# GPIO_EXTENDER.net
KiCad netlist of a schematic drawn in Altium Designer
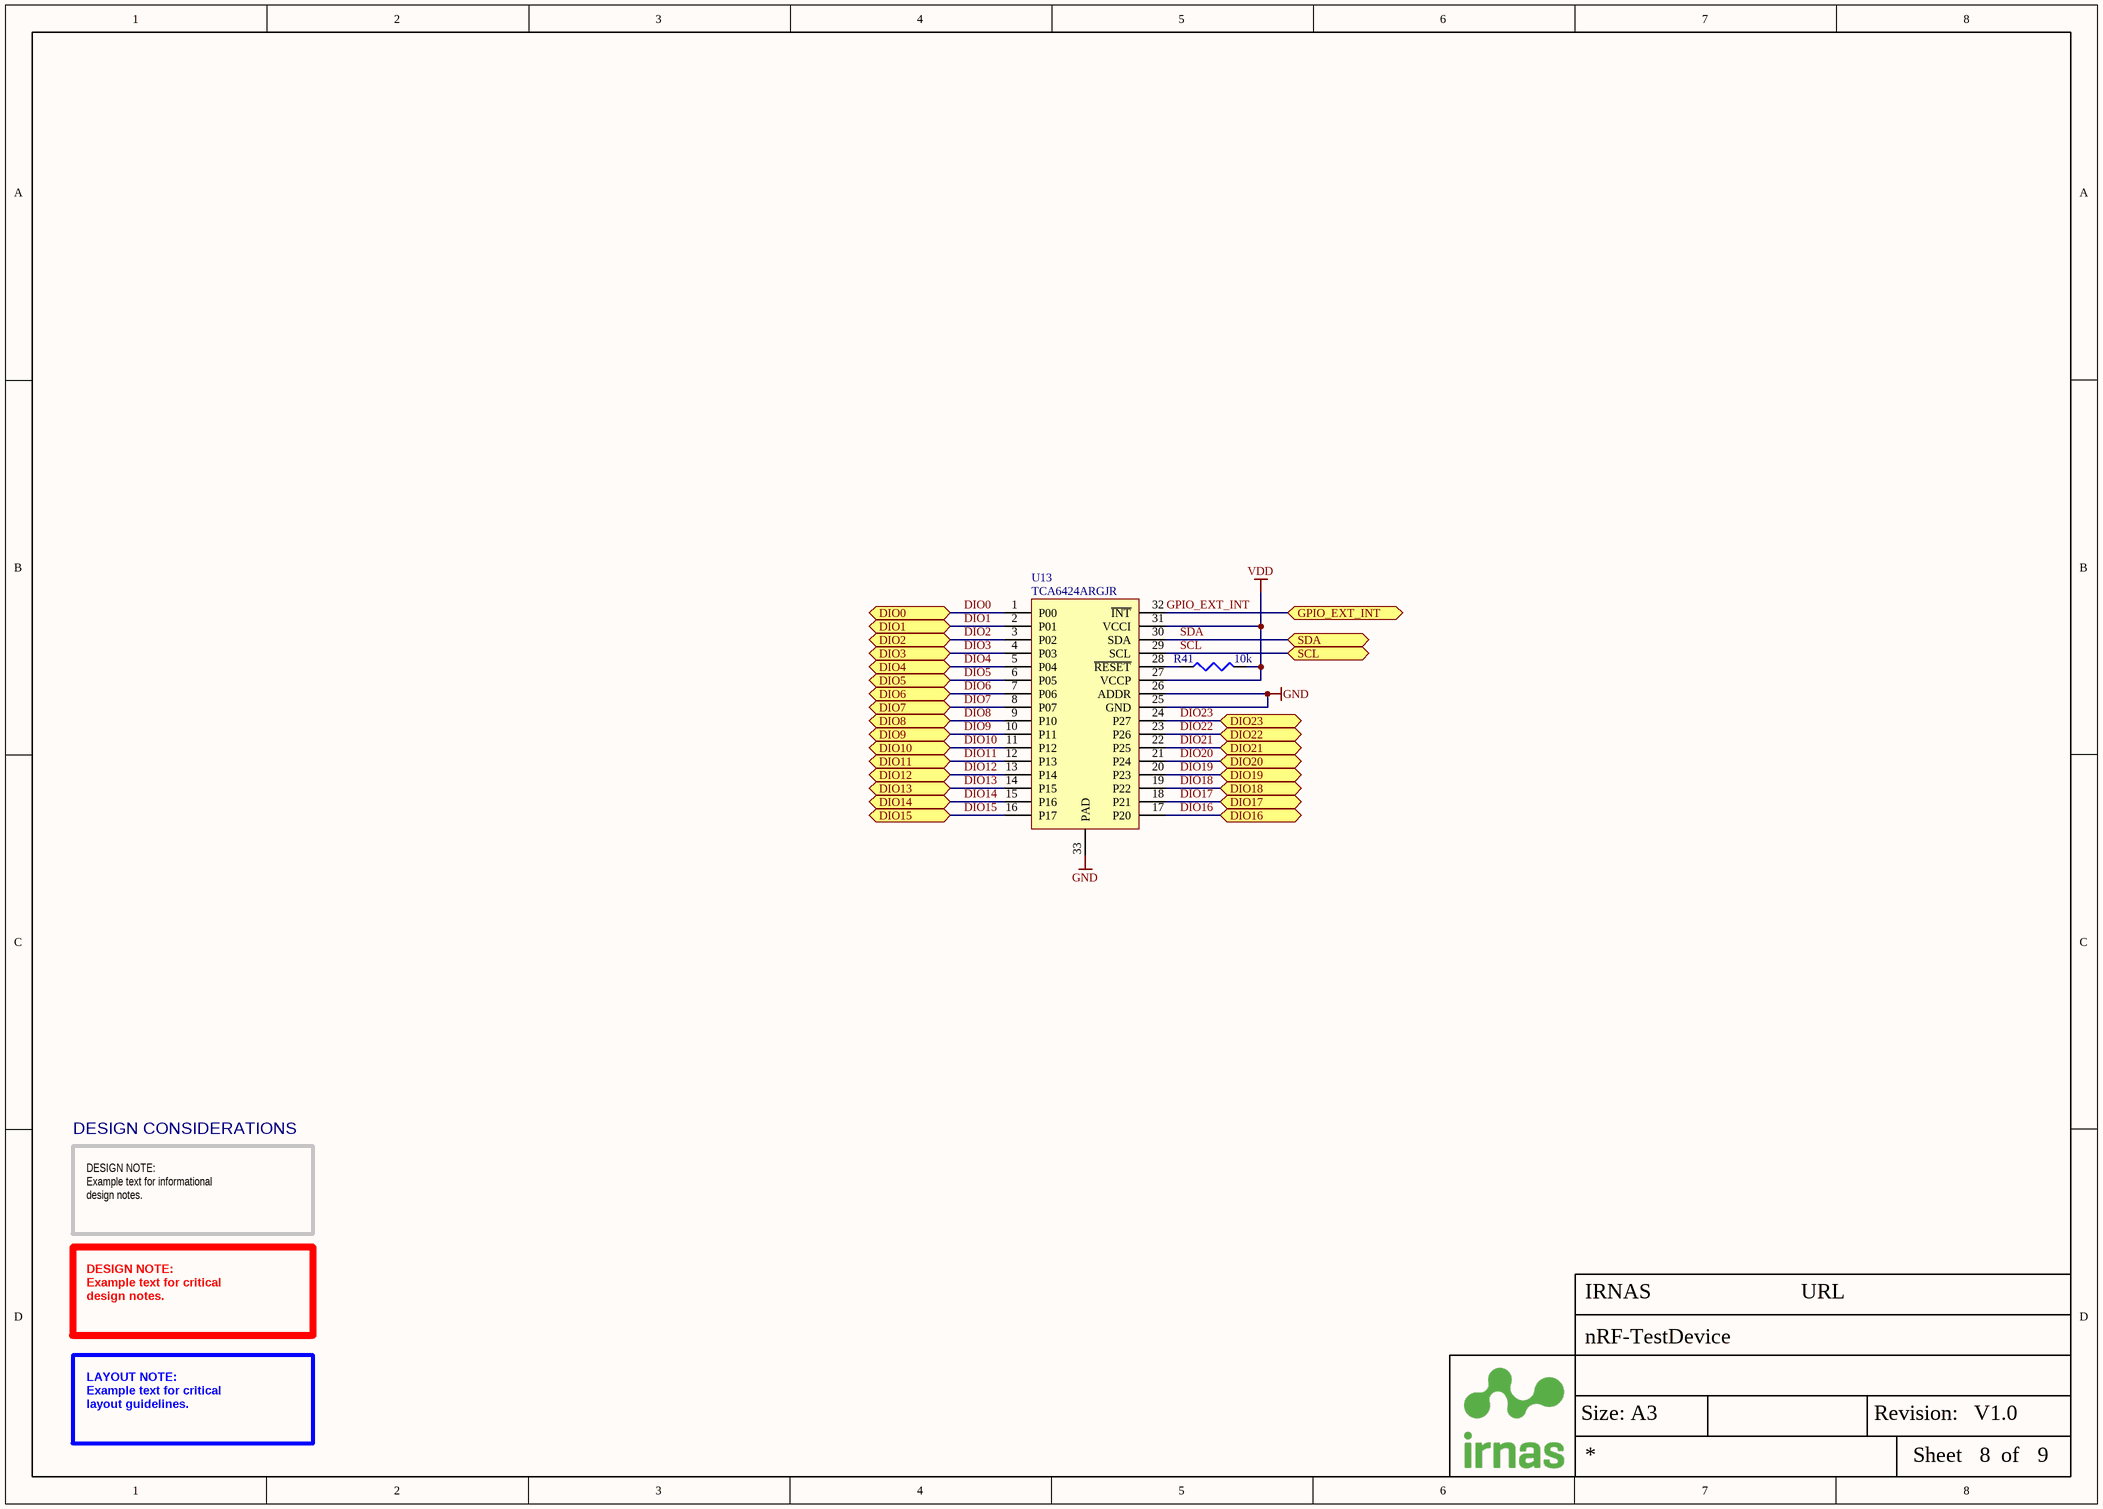
[diagram p0: GPIO_EXTENDER.SchDoc]

(export (version "E")
  (design (tool "Eeschema 10.0.6"))
  (components
    (comp (ref "R41")
      (value "10k")
      (footprint "RES0402")
      (fields
        (field (name "MANUFACTURER") "Multicomp")
        (field (name "MANUFACTURER PART NUMBER") "MCWR04X1002FTL")
        (field (name "TOLERANCE") "1%")
      )
      (libsource (lib "Passive") (part "R - 10k/0402"))
    )
    (comp (ref "U13")
      (value "TCA6424ARGJR")
      (footprint "UQFN 32")
      (description "I/O Expander, 24bit, 400 kHz, I2C, SMBus, 1.65 V, 5.5 V, UQFN")
      (libsource (lib "Active") (part "INT - TCA6424ARGJR"))
    )
  )
  (nets
    (net (code "1") (name "/DIO0") (class "Default")
      (node (ref "U13") (pin "1") (pinfunction "P00_1") (pintype "passive"))
    )
    (net (code "2") (name "/DIO1") (class "Default")
      (node (ref "U13") (pin "2") (pinfunction "P01_2") (pintype "passive"))
    )
    (net (code "3") (name "/DIO2") (class "Default")
      (node (ref "U13") (pin "3") (pinfunction "P02_3") (pintype "passive"))
    )
    (net (code "4") (name "/DIO3") (class "Default")
      (node (ref "U13") (pin "4") (pinfunction "P03_4") (pintype "passive"))
    )
    (net (code "5") (name "/DIO4") (class "Default")
      (node (ref "U13") (pin "5") (pinfunction "P04_5") (pintype "passive"))
    )
    (net (code "6") (name "/DIO5") (class "Default")
      (node (ref "U13") (pin "6") (pinfunction "P05_6") (pintype "passive"))
    )
    (net (code "7") (name "/DIO6") (class "Default")
      (node (ref "U13") (pin "7") (pinfunction "P06_7") (pintype "passive"))
    )
    (net (code "8") (name "/DIO7") (class "Default")
      (node (ref "U13") (pin "8") (pinfunction "P07_8") (pintype "passive"))
    )
    (net (code "9") (name "/DIO8") (class "Default")
      (node (ref "U13") (pin "9") (pinfunction "P10_9") (pintype "passive"))
    )
    (net (code "10") (name "/DIO9") (class "Default")
      (node (ref "U13") (pin "10") (pinfunction "P11_10") (pintype "passive"))
    )
    (net (code "11") (name "/DIO10") (class "Default")
      (node (ref "U13") (pin "11") (pinfunction "P12_11") (pintype "passive"))
    )
    (net (code "12") (name "/DIO11") (class "Default")
      (node (ref "U13") (pin "12") (pinfunction "P13_12") (pintype "passive"))
    )
    (net (code "13") (name "/DIO12") (class "Default")
      (node (ref "U13") (pin "13") (pinfunction "P14_13") (pintype "passive"))
    )
    (net (code "14") (name "/DIO13") (class "Default")
      (node (ref "U13") (pin "14") (pinfunction "P15_14") (pintype "passive"))
    )
    (net (code "15") (name "/DIO14") (class "Default")
      (node (ref "U13") (pin "15") (pinfunction "P16_15") (pintype "passive"))
    )
    (net (code "16") (name "/DIO15") (class "Default")
      (node (ref "U13") (pin "16") (pinfunction "P17_16") (pintype "passive"))
    )
    (net (code "17") (name "/DIO16") (class "Default")
      (node (ref "U13") (pin "17") (pinfunction "P20_17") (pintype "passive"))
    )
    (net (code "18") (name "/DIO17") (class "Default")
      (node (ref "U13") (pin "18") (pinfunction "P21_18") (pintype "passive"))
    )
    (net (code "19") (name "/DIO18") (class "Default")
      (node (ref "U13") (pin "19") (pinfunction "P22_19") (pintype "passive"))
    )
    (net (code "20") (name "/DIO19") (class "Default")
      (node (ref "U13") (pin "20") (pinfunction "P23_20") (pintype "passive"))
    )
    (net (code "21") (name "/DIO20") (class "Default")
      (node (ref "U13") (pin "21") (pinfunction "P24_21") (pintype "passive"))
    )
    (net (code "22") (name "/DIO21") (class "Default")
      (node (ref "U13") (pin "22") (pinfunction "P25_22") (pintype "passive"))
    )
    (net (code "23") (name "/DIO22") (class "Default")
      (node (ref "U13") (pin "23") (pinfunction "P26_23") (pintype "passive"))
    )
    (net (code "24") (name "/DIO23") (class "Default")
      (node (ref "U13") (pin "24") (pinfunction "P27_24") (pintype "passive"))
    )
    (net (code "25") (name "/GPIO_EXT_INT") (class "Default")
      (node (ref "U13") (pin "32") (pinfunction "~{INT}_32") (pintype "passive"))
    )
    (net (code "26") (name "/SCL") (class "Default")
      (node (ref "U13") (pin "29") (pinfunction "SCL_29") (pintype "passive"))
    )
    (net (code "27") (name "/SDA") (class "Default")
      (node (ref "U13") (pin "30") (pinfunction "SDA_30") (pintype "passive"))
    )
    (net (code "28") (name "GND") (class "Default")
      (node (ref "U13") (pin "25") (pinfunction "GND_25") (pintype "passive"))
      (node (ref "U13") (pin "26") (pinfunction "ADDR_26") (pintype "passive"))
      (node (ref "U13") (pin "33") (pinfunction "PAD_33") (pintype "passive"))
    )
    (net (code "29") (name "Net-(U13-~{RESET})") (class "Default")
      (node (ref "R41") (pin "1") (pinfunction "1_1") (pintype "passive"))
      (node (ref "U13") (pin "28") (pinfunction "~{RESET}_28") (pintype "passive"))
    )
    (net (code "30") (name "VDD") (class "Default")
      (node (ref "R41") (pin "2") (pinfunction "2_2") (pintype "passive"))
      (node (ref "U13") (pin "27") (pinfunction "VCCP_27") (pintype "passive"))
      (node (ref "U13") (pin "31") (pinfunction "VCCI_31") (pintype "passive"))
    )
  )
)
